# UI.net
KiCad netlist of a schematic drawn in Altium Designer
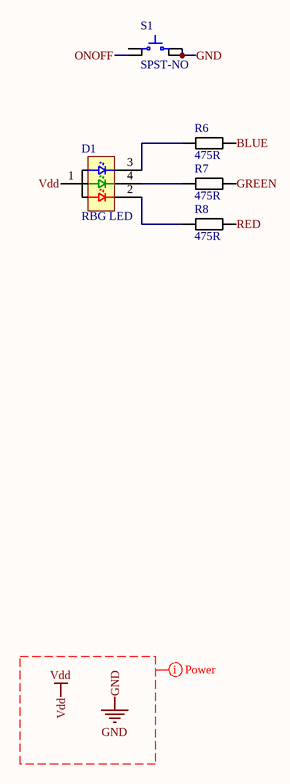
[diagram p0: UI.SchDoc]

(export (version "E")
  (design (tool "Eeschema 10.0.6"))
  (components
    (comp (ref "D1")
      (value "RBG LED")
      (footprint "LED 0101/0404 RGB")
      (description "LED 0404 RBG")
      (fields (field (name "PART NUMBER") "SML-LX0404SIUPGUSB") (field (name "MANUFACTURER") "Lumex"))
      (libsource (lib "ekuore-library") (part "LED RBG"))
    )
    (comp (ref "R6")
      (value "475R")
      (footprint "RES 0402/1005")
      (description "RES 0402 475R 1%  63mW")
      (fields (field (name "PART NUMBER") "RC0402FR-07475RL") (field (name "MANUFACTURER") "Yageo"))
      (libsource (lib "ekuore-library") (part "Resistor"))
    )
    (comp (ref "R7")
      (value "475R")
      (footprint "RES 0402/1005")
      (description "RES 0402 475R 1%  63mW")
      (fields (field (name "PART NUMBER") "RC0402FR-07475RL") (field (name "MANUFACTURER") "Yageo"))
      (libsource (lib "ekuore-library") (part "Resistor"))
    )
    (comp (ref "R8")
      (value "475R")
      (footprint "RES 0402/1005")
      (description "RES 0402 475R 1%  63mW")
      (fields (field (name "PART NUMBER") "RC0402FR-07475RL") (field (name "MANUFACTURER") "Yageo"))
      (libsource (lib "ekuore-library") (part "Resistor"))
    )
    (comp (ref "S1")
      (value "SPST-NO")
      (footprint "Panasonic evqp7")
      (description "Switch Tactile N.O. SPST Right Angle 0.05A 12V")
      (fields (field (name "PART NUMBER") "EVQ-P7A01P") (field (name "MANUFACTURER") "Panasonic"))
      (libsource (lib "ekuore-library") (part "SPST-NO 4 PIN"))
    )
  )
  (nets
    (net (code "1") (name "/BLUE") (class "Default")
      (node (ref "R6") (pin "2") (pinfunction "2_2") (pintype "passive"))
    )
    (net (code "2") (name "/GREEN") (class "Default")
      (node (ref "R7") (pin "2") (pinfunction "2_2") (pintype "passive"))
    )
    (net (code "3") (name "/ONOFF") (class "Default")
      (node (ref "S1") (pin "1'") (pinfunction "1'_1'") (pintype "passive"))
    )
    (net (code "4") (name "/RED") (class "Default")
      (node (ref "R8") (pin "2") (pinfunction "2_2") (pintype "passive"))
    )
    (net (code "5") (name "GND") (class "Default")
      (node (ref "S1") (pin "2") (pinfunction "2_2") (pintype "passive"))
      (node (ref "S1") (pin "2'") (pinfunction "2'_2'") (pintype "passive"))
    )
    (net (code "6") (name "Net-(D1-C2)") (class "Default")
      (node (ref "D1") (pin "2") (pinfunction "C2_2") (pintype "passive"))
      (node (ref "R8") (pin "1") (pinfunction "1_1") (pintype "passive"))
    )
    (net (code "7") (name "Net-(D1-C3)") (class "Default")
      (node (ref "D1") (pin "3") (pinfunction "C3_3") (pintype "passive"))
      (node (ref "R6") (pin "1") (pinfunction "1_1") (pintype "passive"))
    )
    (net (code "8") (name "Net-(D1-C4)") (class "Default")
      (node (ref "D1") (pin "4") (pinfunction "C4_4") (pintype "passive"))
      (node (ref "R7") (pin "1") (pinfunction "1_1") (pintype "passive"))
    )
    (net (code "9") (name "Vdd") (class "Default")
      (node (ref "D1") (pin "1") (pinfunction "A_1") (pintype "passive"))
    )
    (net (code "10") (name "unconnected-(S1-Pad1)") (class "Default")
      (node (ref "S1") (pin "1") (pinfunction "1_1") (pintype "passive"))
    )
  )
)
